# ESP32_with_USBC.net
KiCad netlist of a schematic drawn in Altium Designer
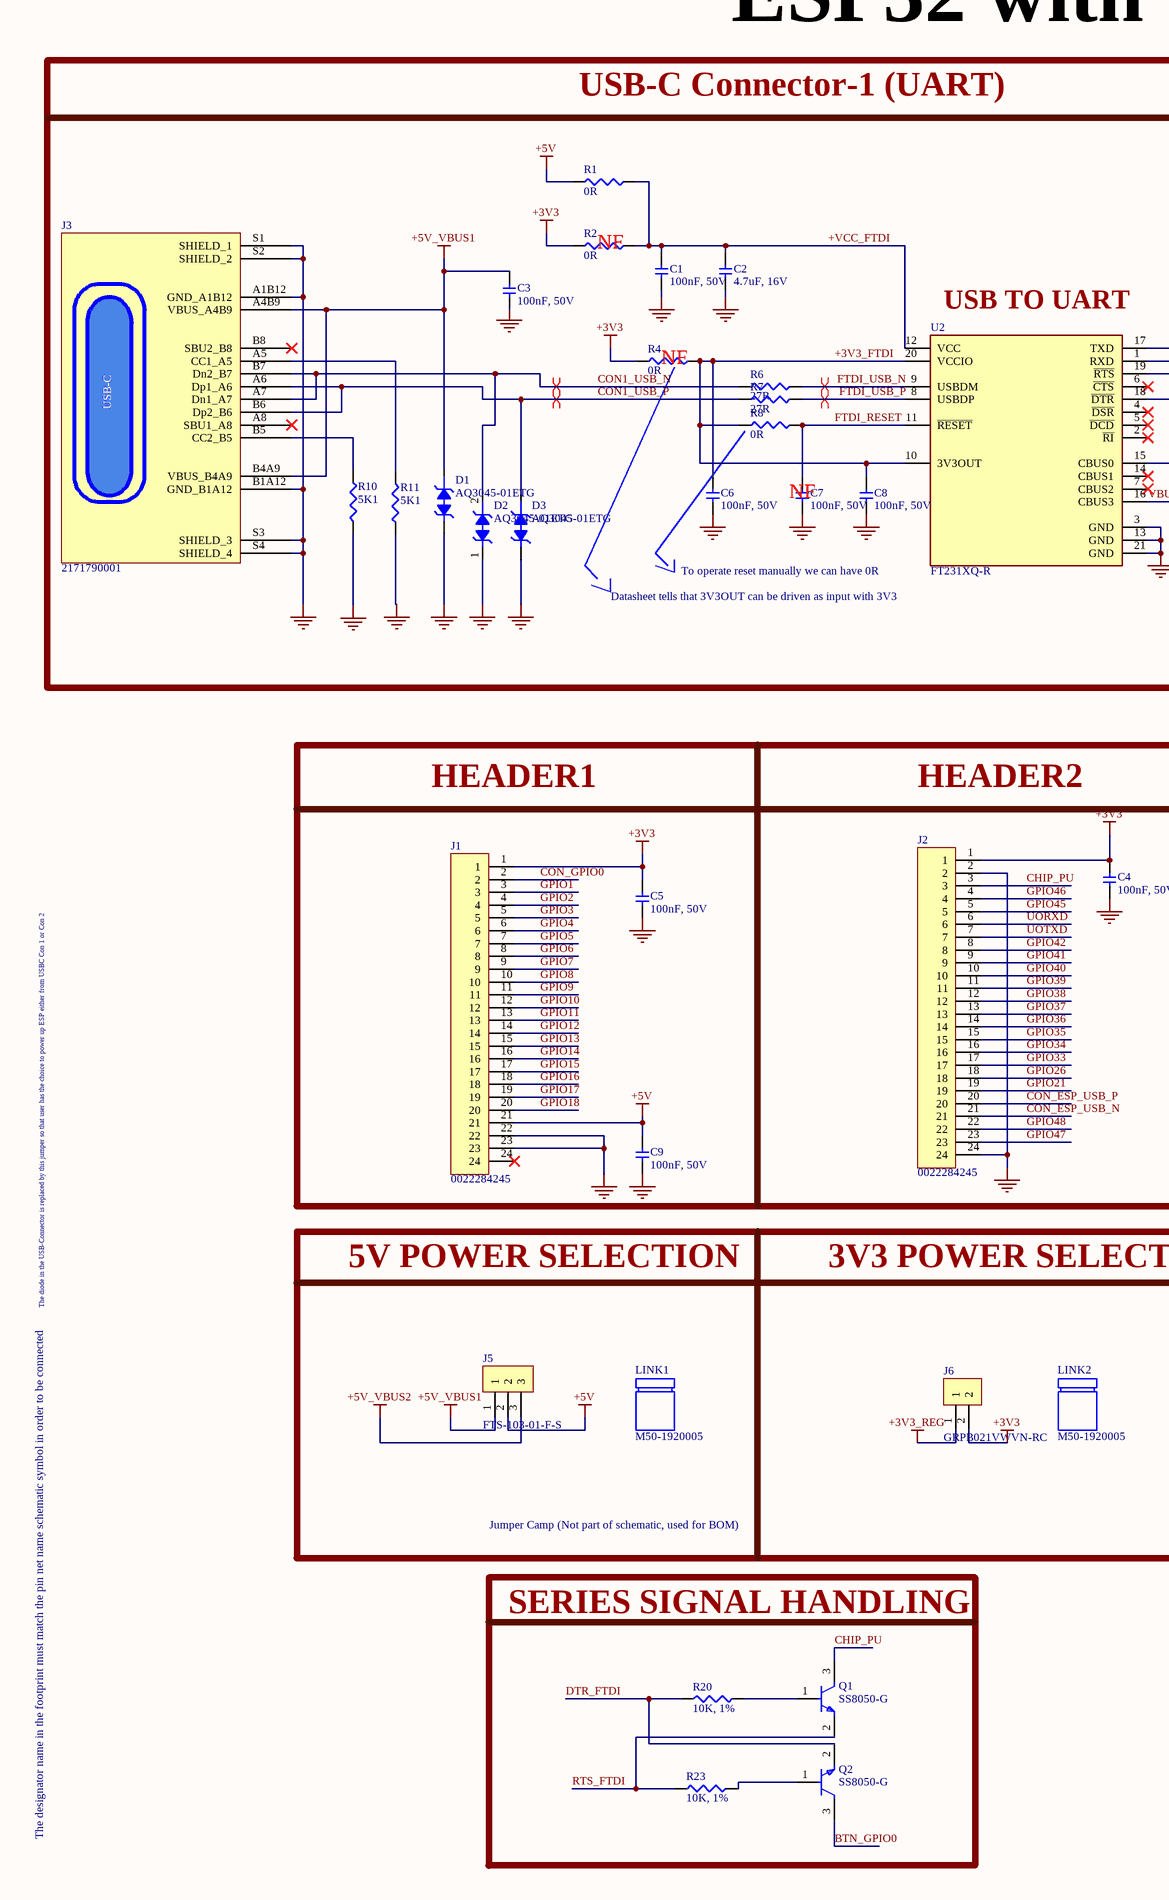
[diagram p0: ESP32 with USBC.SchDoc, left]
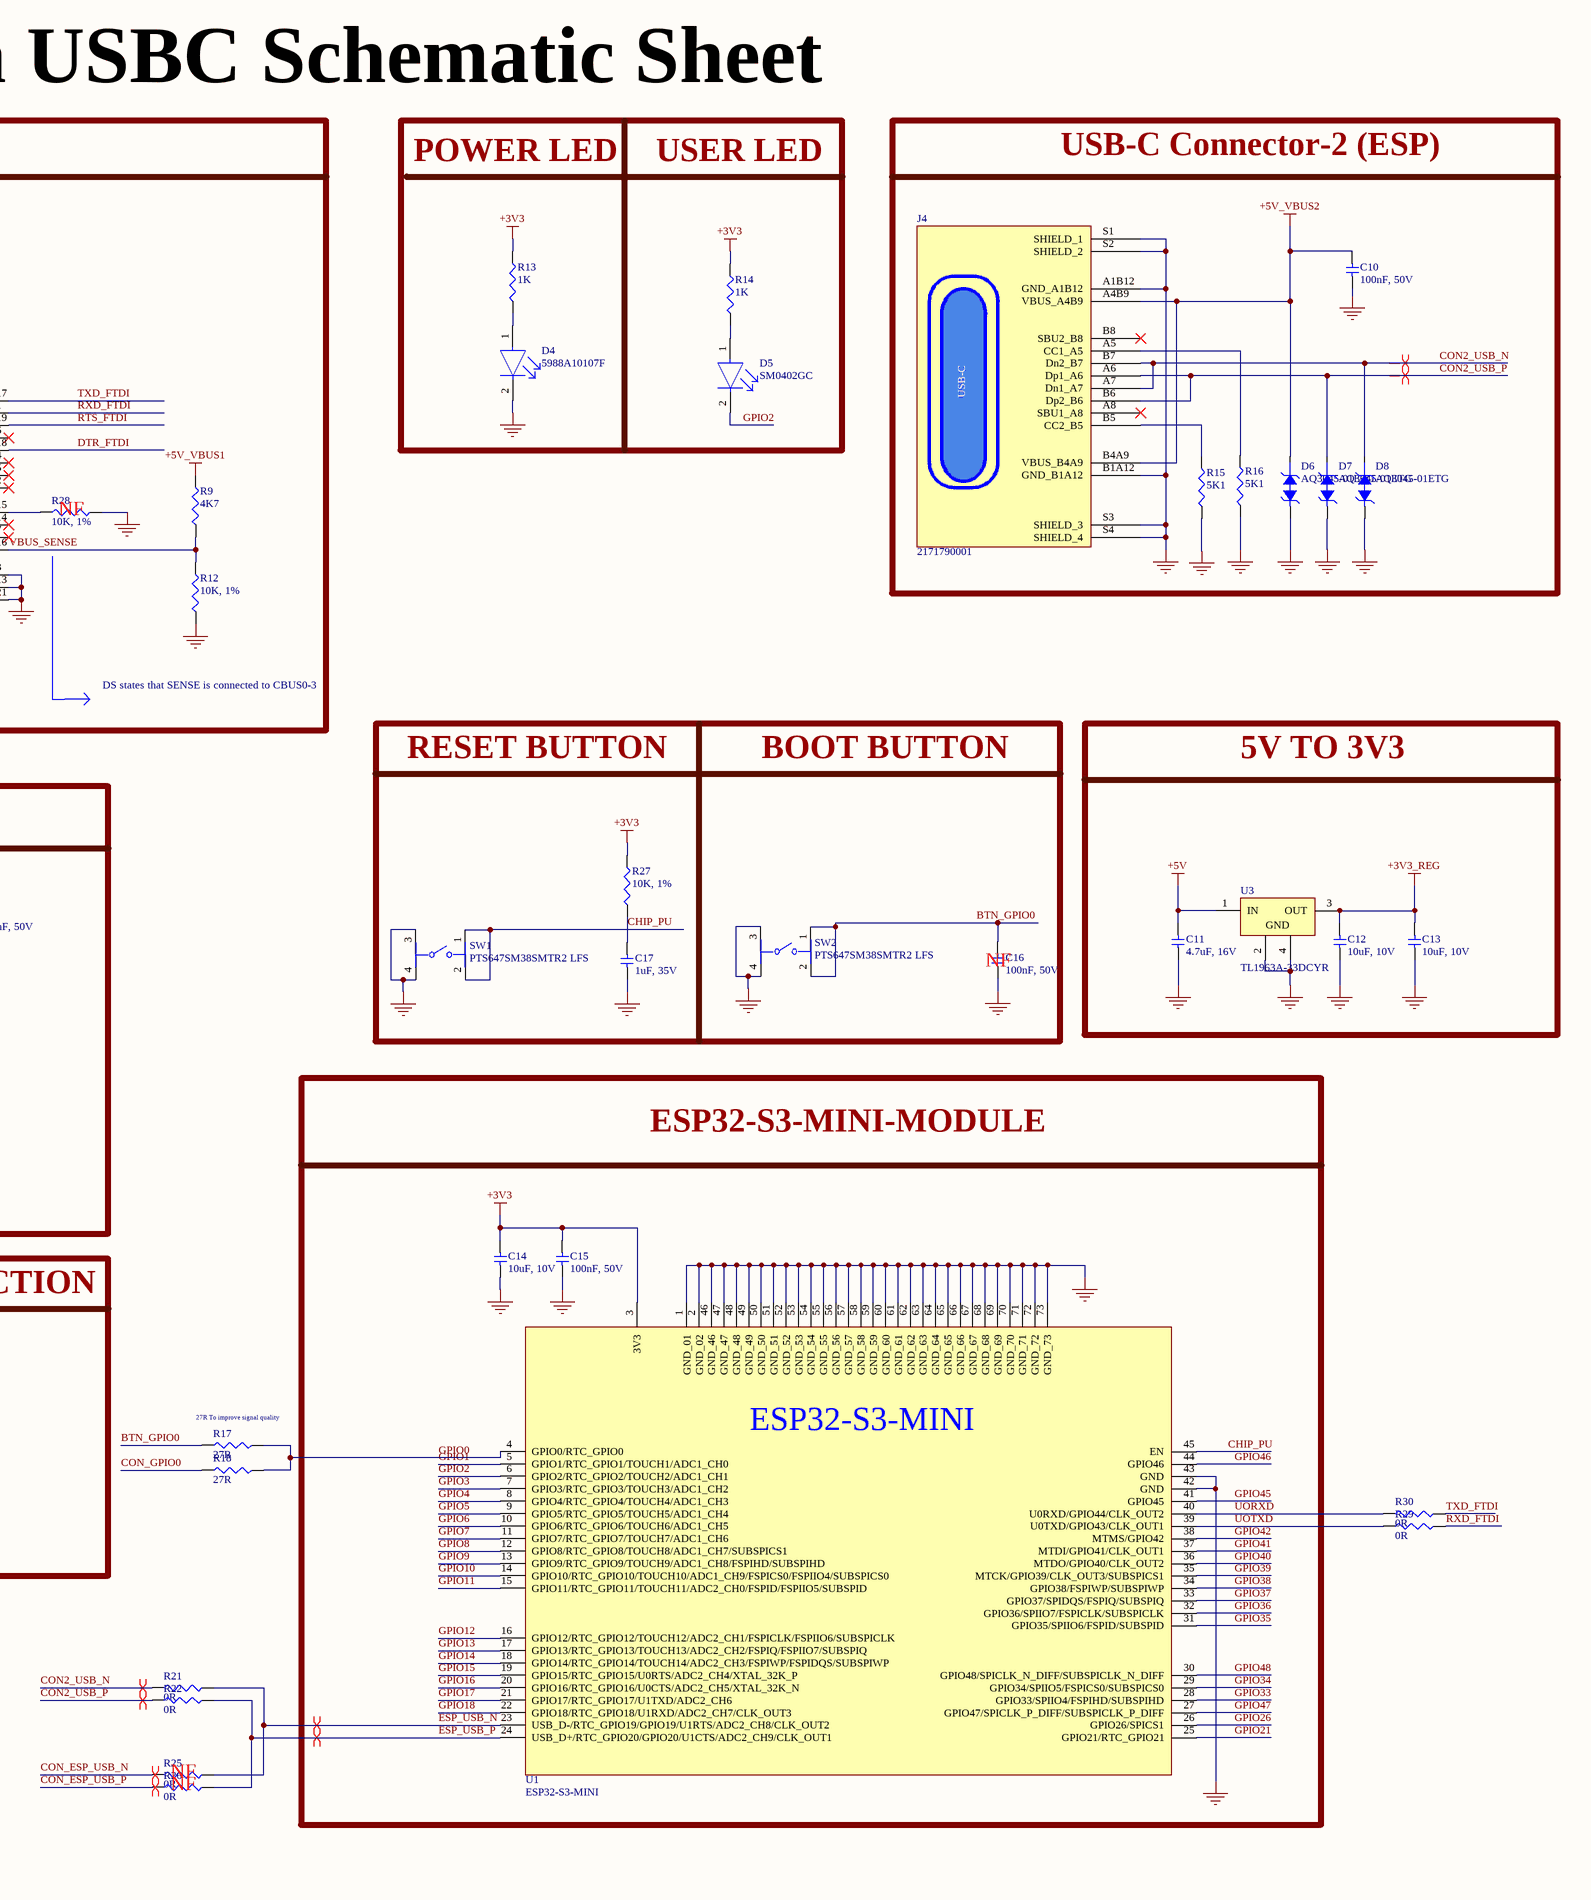
[diagram p1: ESP32 with USBC.SchDoc, right]

(export (version "E")
  (design (tool "Eeschema 10.0.6"))
  (components
    (comp (ref "C1")
      (value "100nF, 50V")
      (footprint "CAPC1005X55N")
      (description "10V 100nF X7R ±10% 0402 Multilayer Ceramic Capacitors MLCC - SMD/SMT ROHS")
      (fields
        (field (name "MANUFACTURER") "Samsung")
        (field (name "MANUFACTURER PART NUMBER") "CL05B104KP5NNNC")
      )
      (libsource (lib "Schlib") (part "CL05B104KP5NNNC"))
    )
    (comp (ref "C2")
      (value "4.7uF, 16V")
      (footprint "CAPC1005X55N")
      (description "CAP CER 4.7UF 16V X5R 0402")
      (fields
        (field (name "MANUFACTURER") "Samsung")
        (field (name "MANUFACTURER PART NUMBER") "CL05A475MO5NUNC")
      )
      (libsource (lib "Schlib") (part "CL05A475MO5NUNC (2)"))
    )
    (comp (ref "C3")
      (value "100nF, 50V")
      (footprint "CAPC1005X55N")
      (description "10V 100nF X7R ±10% 0402 Multilayer Ceramic Capacitors MLCC - SMD/SMT ROHS")
      (fields
        (field (name "MANUFACTURER") "Samsung")
        (field (name "MANUFACTURER PART NUMBER") "CL05B104KP5NNNC")
      )
      (libsource (lib "Schlib") (part "CL05B104KP5NNNC"))
    )
    (comp (ref "C4")
      (value "100nF, 50V")
      (footprint "CAPC1005X55N")
      (description "10V 100nF X7R ±10% 0402 Multilayer Ceramic Capacitors MLCC - SMD/SMT ROHS")
      (fields
        (field (name "MANUFACTURER") "Samsung")
        (field (name "MANUFACTURER PART NUMBER") "CL05B104KP5NNNC")
      )
      (libsource (lib "Schlib") (part "CL05B104KP5NNNC"))
    )
    (comp (ref "C5")
      (value "100nF, 50V")
      (footprint "CAPC1005X55N")
      (description "10V 100nF X7R ±10% 0402 Multilayer Ceramic Capacitors MLCC - SMD/SMT ROHS")
      (fields
        (field (name "MANUFACTURER") "Samsung")
        (field (name "MANUFACTURER PART NUMBER") "CL05B104KP5NNNC")
      )
      (libsource (lib "Schlib") (part "CL05B104KP5NNNC"))
    )
    (comp (ref "C6")
      (value "100nF, 50V")
      (footprint "CAPC1005X55N")
      (description "10V 100nF X7R ±10% 0402 Multilayer Ceramic Capacitors MLCC - SMD/SMT ROHS")
      (fields
        (field (name "MANUFACTURER") "Samsung")
        (field (name "MANUFACTURER PART NUMBER") "CL05B104KP5NNNC")
      )
      (libsource (lib "Schlib") (part "CL05B104KP5NNNC"))
    )
    (comp (ref "C7")
      (value "100nF, 50V")
      (footprint "CAPC1005X55N")
      (description "10V 100nF X7R ±10% 0402 Multilayer Ceramic Capacitors MLCC - SMD/SMT ROHS")
      (fields
        (field (name "MANUFACTURER") "Samsung")
        (field (name "MANUFACTURER PART NUMBER") "CL05B104KP5NNNC")
      )
      (libsource (lib "Schlib") (part "CL05B104KP5NNNC"))
    )
    (comp (ref "C8")
      (value "100nF, 50V")
      (footprint "CAPC1005X55N")
      (description "10V 100nF X7R ±10% 0402 Multilayer Ceramic Capacitors MLCC - SMD/SMT ROHS")
      (fields
        (field (name "MANUFACTURER") "Samsung")
        (field (name "MANUFACTURER PART NUMBER") "CL05B104KP5NNNC")
      )
      (libsource (lib "Schlib") (part "CL05B104KP5NNNC"))
    )
    (comp (ref "C9")
      (value "100nF, 50V")
      (footprint "CAPC1005X55N")
      (description "10V 100nF X7R ±10% 0402 Multilayer Ceramic Capacitors MLCC - SMD/SMT ROHS")
      (fields
        (field (name "MANUFACTURER") "Samsung")
        (field (name "MANUFACTURER PART NUMBER") "CL05B104KP5NNNC")
      )
      (libsource (lib "Schlib") (part "CL05B104KP5NNNC"))
    )
    (comp (ref "C10")
      (value "100nF, 50V")
      (footprint "CAPC1005X55N")
      (description "10V 100nF X7R ±10% 0402 Multilayer Ceramic Capacitors MLCC - SMD/SMT ROHS")
      (fields
        (field (name "MANUFACTURER") "Samsung")
        (field (name "MANUFACTURER PART NUMBER") "CL05B104KP5NNNC")
      )
      (libsource (lib "Schlib") (part "CL05B104KP5NNNC"))
    )
    (comp (ref "C11")
      (value "4.7uF, 16V")
      (footprint "CAPC1005X55N")
      (description "CAP CER 4.7UF 16V X5R 0402")
      (fields
        (field (name "MANUFACTURER") "Samsung")
        (field (name "MANUFACTURER PART NUMBER") "CL05A475MO5NUNC")
      )
      (libsource (lib "Schlib") (part "CL05A475MO5NUNC (2)"))
    )
    (comp (ref "C12")
      (value "10uF, 10V")
      (footprint "CAPC1005X55N")
      (description "10 µF ±20% 10V Ceramic Capacitor X5R 0402 (1005 Metric)")
      (fields
        (field (name "MANUFACTURER") "Samsung")
        (field (name "MANUFACTURER PART NUMBER") "CL05A106MP8NUB8")
      )
      (libsource (lib "Schlib") (part "CL05A106MP8NUB8"))
    )
    (comp (ref "C13")
      (value "10uF, 10V")
      (footprint "CAPC1005X55N")
      (description "10 µF ±20% 10V Ceramic Capacitor X5R 0402 (1005 Metric)")
      (fields
        (field (name "MANUFACTURER") "Samsung")
        (field (name "MANUFACTURER PART NUMBER") "CL05A106MP8NUB8")
      )
      (libsource (lib "Schlib") (part "CL05A106MP8NUB8"))
    )
    (comp (ref "C14")
      (value "10uF, 10V")
      (footprint "CAPC1005X55N")
      (description "10 µF ±20% 10V Ceramic Capacitor X5R 0402 (1005 Metric)")
      (fields
        (field (name "MANUFACTURER") "Samsung")
        (field (name "MANUFACTURER PART NUMBER") "CL05A106MP8NUB8")
      )
      (libsource (lib "Schlib") (part "CL05A106MP8NUB8"))
    )
    (comp (ref "C15")
      (value "100nF, 50V")
      (footprint "CAPC1005X55N")
      (description "10V 100nF X7R ±10% 0402 Multilayer Ceramic Capacitors MLCC - SMD/SMT ROHS")
      (fields
        (field (name "MANUFACTURER") "Samsung")
        (field (name "MANUFACTURER PART NUMBER") "CL05B104KP5NNNC")
      )
      (libsource (lib "Schlib") (part "CL05B104KP5NNNC"))
    )
    (comp (ref "C16")
      (value "100nF, 50V")
      (footprint "CAPC1005X55N")
      (description "10V 100nF X7R ±10% 0402 Multilayer Ceramic Capacitors MLCC - SMD/SMT ROHS")
      (fields
        (field (name "MANUFACTURER") "Samsung")
        (field (name "MANUFACTURER PART NUMBER") "CL05B104KP5NNNC")
      )
      (libsource (lib "Schlib") (part "CL05B104KP5NNNC"))
    )
    (comp (ref "C17")
      (value "1uF, 35V")
      (footprint "CAPC1005X55N")
      (description "CAP CER 1UF 35V X5R 0402")
      (fields
        (field (name "MANUFACTURER") "Samsung")
        (field (name "MANUFACTURER PART NUMBER") "CL05A105KL5NRNC")
      )
      (libsource (lib "Schlib") (part "CL05A105KL5NRNC"))
    )
    (comp (ref "D1")
      (value "AQ3045-01ETG")
      (footprint "SOD882")
      (description "TVS DIODE 5.3VWM 12VC SOD882")
      (fields (field (name "MANUFACTURER") "Littelfuse") (field (name "LCSC PART NUMBER") "C3710326"))
      (libsource (lib "Schlib") (part "AQ3045-01ETG"))
    )
    (comp (ref "D2")
      (value "AQ3045-01ETG")
      (footprint "SOD882")
      (description "TVS DIODE 5.3VWM 12VC SOD882")
      (fields (field (name "MANUFACTURER") "Littelfuse") (field (name "LCSC PART NUMBER") "C3710326"))
      (libsource (lib "") (part "AQ3045-01ETG_1"))
    )
    (comp (ref "D3")
      (value "AQ3045-01ETG")
      (footprint "SOD882")
      (description "TVS DIODE 5.3VWM 12VC SOD882")
      (fields (field (name "MANUFACTURER") "Littelfuse") (field (name "LCSC PART NUMBER") "C3710326"))
      (libsource (lib "Schlib") (part "AQ3045-01ETG"))
    )
    (comp (ref "D4")
      (value "5988A10107F")
      (footprint "5988A10107F")
      (description "LED RED 635NM 0402 SMD")
      (fields (field (name "MANUFACTURER") "Dialight") (field (name "LCSC PART NUMBER") "C6095258"))
      (libsource (lib "Schlib") (part "5988A10107F"))
    )
    (comp (ref "D5")
      (value "SM0402GC")
      (footprint "FP-SM0402GC-MFG")
      (description "LED GREEN CLEAR 0402 SMD")
      (fields (field (name "MANUFACTURER") "Bivar") (field (name "LCSC PART NUMBER") "C6488778"))
      (libsource (lib "Schlib") (part "SM0402GC"))
    )
    (comp (ref "D6")
      (value "AQ3045-01ETG")
      (footprint "SOD882")
      (description "TVS DIODE 5.3VWM 12VC SOD882")
      (fields (field (name "MANUFACTURER") "Littelfuse") (field (name "LCSC PART NUMBER") "C3710326"))
      (libsource (lib "Schlib") (part "AQ3045-01ETG"))
    )
    (comp (ref "D7")
      (value "AQ3045-01ETG")
      (footprint "SOD882")
      (description "TVS DIODE 5.3VWM 12VC SOD882")
      (fields (field (name "MANUFACTURER") "Littelfuse") (field (name "LCSC PART NUMBER") "C3710326"))
      (libsource (lib "Schlib") (part "AQ3045-01ETG"))
    )
    (comp (ref "D8")
      (value "AQ3045-01ETG")
      (footprint "SOD882")
      (description "TVS DIODE 5.3VWM 12VC SOD882")
      (fields (field (name "MANUFACTURER") "Littelfuse") (field (name "LCSC PART NUMBER") "C3710326"))
      (libsource (lib "Schlib") (part "AQ3045-01ETG"))
    )
    (comp (ref "J1")
      (value "0022284245")
      (footprint "HDR_1X24_2.54MM")
      (description "CONN HEADER VERT 24POS 2.54MM")
      (fields (field (name "MANUFACTURER") "Molex") (field (name "MANUFACTURER PART NUMBER") "22-28-4245"))
      (libsource (lib "Schlib") (part "22-28-4245"))
    )
    (comp (ref "J2")
      (value "0022284245")
      (footprint "HDR_1X24_2.54MM")
      (description "CONN HEADER VERT 24POS 2.54MM")
      (fields (field (name "MANUFACTURER") "Molex") (field (name "MANUFACTURER PART NUMBER") "22-28-4245"))
      (libsource (lib "Schlib") (part "22-28-4245"))
    )
    (comp (ref "J3")
      (value "2171790001")
      (footprint "FP-2171790001-MFG")
      (description "CONN RCP USB2.0 TYP C 24P SMD RA")
      (fields (field (name "MANUFACTURER") "Molex") (field (name "MANUFACTURER PART NUMBER") "217179-0001"))
      (libsource (lib "Schlib") (part "217179-0001"))
    )
    (comp (ref "J4")
      (value "2171790001")
      (footprint "FP-2171790001-MFG")
      (description "CONN RCP USB2.0 TYP C 24P SMD RA")
      (fields (field (name "MANUFACTURER") "Molex") (field (name "MANUFACTURER PART NUMBER") "217179-0001"))
      (libsource (lib "Schlib") (part "217179-0001"))
    )
    (comp (ref "J5")
      (value "FTS-103-01-F-S")
      (footprint "HDR_1X3_1.27MM")
      (description "CONN HEADER VERT 3POS 1.27MM")
      (fields (field (name "MANUFACTURER") "Samtec") (field (name "LCSC PART NUMBER") "C3333578"))
      (libsource (lib "Schlib") (part "FTS-103-01-F-S"))
    )
    (comp (ref "J6")
      (value "GRPB021VWVN-RC")
      (footprint "HDR_1X2_1.27MM")
      (description "CONN HEADER VERT 2POS 1.27MM")
      (fields (field (name "MANUFACTURER") "Sullins") (field (name "LCSC PART NUMBER") "C6050037"))
      (libsource (lib "Schlib") (part "GRPB021VWVN-RC"))
    )
    (comp (ref "LINK1")
      (value "M50-1920005")
      (description "CONN SHUNT 1.27MM RED")
      (fields (field (name "MANUFACTURER") "Harwin"))
      (libsource (lib "Schlib") (part "M50-1920005"))
    )
    (comp (ref "LINK2")
      (value "M50-1920005")
      (description "CONN SHUNT 1.27MM RED")
      (fields (field (name "MANUFACTURER") "Harwin"))
      (libsource (lib "Schlib") (part "M50-1920005"))
    )
    (comp (ref "Q1")
      (value "SS8050-G")
      (footprint "FP-SS8050-G-IPC_B")
      (description "TRANS NPN 25V 1.5A SOT-23-3")
      (fields (field (name "MANUFACTURER") "Comchip") (field (name "LCSC PART NUMBER") "C164886"))
      (libsource (lib "Schlib") (part "SS8050-G"))
    )
    (comp (ref "Q2")
      (value "SS8050-G")
      (footprint "FP-SS8050-G-IPC_B")
      (description "TRANS NPN 25V 1.5A SOT-23-3")
      (fields (field (name "MANUFACTURER") "Comchip") (field (name "LCSC PART NUMBER") "C164886"))
      (libsource (lib "Schlib") (part "SS8050-G"))
    )
    (comp (ref "R1")
      (value "0R")
      (footprint "RESC1005X37N")
      (description "RES 0 OHM JUMPER 1/16W 0402")
      (fields
        (field (name "MANUFACTURER") "Yageo")
        (field (name "MANUFACTURER PART NUMBER") "RC0402JR-070RL")
      )
      (libsource (lib "Schlib") (part "RC0402JR-070RL"))
    )
    (comp (ref "R2")
      (value "0R")
      (footprint "RESC1005X37N")
      (description "RES 0 OHM JUMPER 1/16W 0402")
      (fields
        (field (name "MANUFACTURER") "Yageo")
        (field (name "MANUFACTURER PART NUMBER") "RC0402JR-070RL")
      )
      (libsource (lib "Schlib") (part "RC0402JR-070RL"))
    )
    (comp (ref "R4")
      (value "0R")
      (footprint "RESC1005X37N")
      (description "RES 0 OHM JUMPER 1/16W 0402")
      (fields
        (field (name "MANUFACTURER") "Yageo")
        (field (name "MANUFACTURER PART NUMBER") "RC0402JR-070RL")
      )
      (libsource (lib "Schlib") (part "RC0402JR-070RL"))
    )
    (comp (ref "R6")
      (value "27R")
      (footprint "RESC1005X37N")
      (description "RES 27 OHM 5% 1/16W 0402")
      (fields
        (field (name "MANUFACTURER") "Yageo")
        (field (name "MANUFACTURER PART NUMBER") "RC0402JR-0727RL")
      )
      (libsource (lib "Schlib") (part "RC0402JR-0727RL"))
    )
    (comp (ref "R7")
      (value "27R")
      (footprint "RESC1005X37N")
      (description "RES 27 OHM 5% 1/16W 0402")
      (fields
        (field (name "MANUFACTURER") "Yageo")
        (field (name "MANUFACTURER PART NUMBER") "RC0402JR-0727RL")
      )
      (libsource (lib "Schlib") (part "RC0402JR-0727RL"))
    )
    (comp (ref "R8")
      (value "0R")
      (footprint "RESC1005X37N")
      (description "RES 0 OHM JUMPER 1/16W 0402")
      (fields
        (field (name "MANUFACTURER") "Yageo")
        (field (name "MANUFACTURER PART NUMBER") "RC0402JR-070RL")
      )
      (libsource (lib "Schlib") (part "RC0402JR-070RL"))
    )
    (comp (ref "R9")
      (value "4K7")
      (footprint "RESC1005X37N")
      (description "RES 4.7K OHM 1% 1/16W 0402")
      (fields
        (field (name "MANUFACTURER") "Yageo")
        (field (name "MANUFACTURER PART NUMBER") "RC0402FR-074K7L")
      )
      (libsource (lib "Schlib") (part "RC0402FR-074K7L"))
    )
    (comp (ref "R10")
      (value "5K1")
      (footprint "RESC1005X37N")
      (description "RES SMD 5.1K OHM 1% 1/16W 0402")
      (fields
        (field (name "MANUFACTURER") "Yageo")
        (field (name "MANUFACTURER PART NUMBER") "AC0402FR-075K1L")
      )
      (libsource (lib "Schlib") (part "AC0402FR-075K1L"))
    )
    (comp (ref "R11")
      (value "5K1")
      (footprint "RESC1005X37N")
      (description "RES SMD 5.1K OHM 1% 1/16W 0402")
      (fields
        (field (name "MANUFACTURER") "Yageo")
        (field (name "MANUFACTURER PART NUMBER") "AC0402FR-075K1L")
      )
      (libsource (lib "Schlib") (part "AC0402FR-075K1L"))
    )
    (comp (ref "R12")
      (value "10K, 1%")
      (footprint "RESC1005X37N")
      (description "RES SMD 10K OHM 1% 1/16W 0402")
      (fields
        (field (name "MANUFACTURER") "Yageo")
        (field (name "MANUFACTURER PART NUMBER") "AC0402FR-0710KL")
      )
      (libsource (lib "Schlib") (part "AC0402FR-0710KL"))
    )
    (comp (ref "R13")
      (value "1K")
      (footprint "RESC1005X37N")
      (description "RES 1K OHM 1% 1/16W 0402")
      (fields
        (field (name "MANUFACTURER") "Yageo")
        (field (name "MANUFACTURER PART NUMBER") "RC0402FR-071KL")
      )
      (libsource (lib "Schlib") (part "RC0402FR-071KL"))
    )
    (comp (ref "R14")
      (value "1K")
      (footprint "RESC1005X37N")
      (description "RES 1K OHM 1% 1/16W 0402")
      (fields
        (field (name "MANUFACTURER") "Yageo")
        (field (name "MANUFACTURER PART NUMBER") "RC0402FR-071KL")
      )
      (libsource (lib "Schlib") (part "RC0402FR-071KL"))
    )
    (comp (ref "R15")
      (value "5K1")
      (footprint "RESC1005X37N")
      (description "RES SMD 5.1K OHM 1% 1/16W 0402")
      (fields
        (field (name "MANUFACTURER") "Yageo")
        (field (name "MANUFACTURER PART NUMBER") "AC0402FR-075K1L")
      )
      (libsource (lib "Schlib") (part "AC0402FR-075K1L"))
    )
    (comp (ref "R16")
      (value "5K1")
      (footprint "RESC1005X37N")
      (description "RES SMD 5.1K OHM 1% 1/16W 0402")
      (fields
        (field (name "MANUFACTURER") "Yageo")
        (field (name "MANUFACTURER PART NUMBER") "AC0402FR-075K1L")
      )
      (libsource (lib "Schlib") (part "AC0402FR-075K1L"))
    )
    (comp (ref "R17")
      (value "27R")
      (footprint "RESC1005X37N")
      (description "RES 27 OHM 5% 1/16W 0402")
      (fields
        (field (name "MANUFACTURER") "Yageo")
        (field (name "MANUFACTURER PART NUMBER") "RC0402JR-0727RL")
      )
      (libsource (lib "Schlib") (part "RC0402JR-0727RL"))
    )
    (comp (ref "R18")
      (value "27R")
      (footprint "RESC1005X37N")
      (description "RES 27 OHM 5% 1/16W 0402")
      (fields
        (field (name "MANUFACTURER") "Yageo")
        (field (name "MANUFACTURER PART NUMBER") "RC0402JR-0727RL")
      )
      (libsource (lib "Schlib") (part "RC0402JR-0727RL"))
    )
    (comp (ref "R20")
      (value "10K, 1%")
      (footprint "RESC1005X37N")
      (description "RES SMD 10K OHM 1% 1/16W 0402")
      (fields
        (field (name "MANUFACTURER") "Yageo")
        (field (name "MANUFACTURER PART NUMBER") "AC0402FR-0710KL")
      )
      (libsource (lib "Schlib") (part "AC0402FR-0710KL"))
    )
    (comp (ref "R21")
      (value "0R")
      (footprint "RESC1005X37N")
      (description "RES 0 OHM JUMPER 1/16W 0402")
      (fields
        (field (name "MANUFACTURER") "Yageo")
        (field (name "MANUFACTURER PART NUMBER") "RC0402JR-070RL")
      )
      (libsource (lib "Schlib") (part "RC0402JR-070RL"))
    )
    (comp (ref "R22")
      (value "0R")
      (footprint "RESC1005X37N")
      (description "RES 0 OHM JUMPER 1/16W 0402")
      (fields
        (field (name "MANUFACTURER") "Yageo")
        (field (name "MANUFACTURER PART NUMBER") "RC0402JR-070RL")
      )
      (libsource (lib "Schlib") (part "RC0402JR-070RL"))
    )
    (comp (ref "R23")
      (value "10K, 1%")
      (footprint "RESC1005X37N")
      (description "RES SMD 10K OHM 1% 1/16W 0402")
      (fields
        (field (name "MANUFACTURER") "Yageo")
        (field (name "MANUFACTURER PART NUMBER") "AC0402FR-0710KL")
      )
      (libsource (lib "Schlib") (part "AC0402FR-0710KL"))
    )
    (comp (ref "R25")
      (value "0R")
      (footprint "RESC1005X37N")
      (description "RES 0 OHM JUMPER 1/16W 0402")
      (fields
        (field (name "MANUFACTURER") "Yageo")
        (field (name "MANUFACTURER PART NUMBER") "RC0402JR-070RL")
      )
      (libsource (lib "Schlib") (part "RC0402JR-070RL"))
    )
    (comp (ref "R26")
      (value "0R")
      (footprint "RESC1005X37N")
      (description "RES 0 OHM JUMPER 1/16W 0402")
      (fields
        (field (name "MANUFACTURER") "Yageo")
        (field (name "MANUFACTURER PART NUMBER") "RC0402JR-070RL")
      )
      (libsource (lib "Schlib") (part "RC0402JR-070RL"))
    )
    (comp (ref "R27")
      (value "10K, 1%")
      (footprint "RESC1005X37N")
      (description "RES SMD 10K OHM 1% 1/16W 0402")
      (fields
        (field (name "MANUFACTURER") "Yageo")
        (field (name "MANUFACTURER PART NUMBER") "AC0402FR-0710KL")
      )
      (libsource (lib "Schlib") (part "AC0402FR-0710KL"))
    )
    (comp (ref "R28")
      (value "10K, 1%")
      (footprint "RESC1005X37N")
      (description "RES SMD 10K OHM 1% 1/16W 0402")
      (fields
        (field (name "MANUFACTURER") "Yageo")
        (field (name "MANUFACTURER PART NUMBER") "AC0402FR-0710KL")
      )
      (libsource (lib "Schlib") (part "AC0402FR-0710KL"))
    )
    (comp (ref "R29")
      (value "0R")
      (footprint "RESC1005X37N")
      (description "RES 0 OHM JUMPER 1/16W 0402")
      (fields
        (field (name "MANUFACTURER") "Yageo")
        (field (name "MANUFACTURER PART NUMBER") "RC0402JR-070RL")
      )
      (libsource (lib "Schlib") (part "RC0402JR-070RL"))
    )
    (comp (ref "R30")
      (value "0R")
      (footprint "RESC1005X37N")
      (description "RES 0 OHM JUMPER 1/16W 0402")
      (fields
        (field (name "MANUFACTURER") "Yageo")
        (field (name "MANUFACTURER PART NUMBER") "RC0402JR-070RL")
      )
      (libsource (lib "Schlib") (part "RC0402JR-070RL"))
    )
    (comp (ref "SW1")
      (value "PTS647SM38SMTR2 LFS")
      (footprint "FP-PTS647SM38SMTR2LFS-MFG")
      (description "SWITCH TACTILE SPST-NO 0.05A 12V")
      (fields
        (field (name "MANUFACTURER") "ITT C&K")
        (field (name "MANUFACTURER PART NUMBER") "PTS647SM38SMTR2LFS")
      )
      (libsource (lib "Schlib") (part "PTS647SM38SMTR2LFS"))
    )
    (comp (ref "SW2")
      (value "PTS647SM38SMTR2 LFS")
      (footprint "FP-PTS647SM38SMTR2LFS-MFG")
      (description "SWITCH TACTILE SPST-NO 0.05A 12V")
      (fields
        (field (name "MANUFACTURER") "ITT C&K")
        (field (name "MANUFACTURER PART NUMBER") "PTS647SM38SMTR2LFS")
      )
      (libsource (lib "Schlib") (part "PTS647SM38SMTR2LFS"))
    )
    (comp (ref "U1")
      (value "ESP32-S3-MINI")
      (footprint "XCVR_ESP32-S3-MINI-1-N8")
      (description "SMD module, ESP32-S3FN8, 8 MB SPI flash, PCB antenna")
      (fields
        (field (name "MANUFACTURER") "Espressif Systems")
        (field (name "MANUFACTURER PART NUMBER") "ESP32-S3-MINI-1-N8")
      )
      (libsource (lib "Schlib") (part "ESP32-S3-MINI-1-N8"))
    )
    (comp (ref "U2")
      (value "FT231XQ-R")
      (footprint "FP-QFN-20-IPC_B")
      (description "IC USB SERIAL FULL UART 20QFNOS")
      (fields (field (name "MANUFACTURER") "FTDI") (field (name "LCSC PART NUMBER") "C132159"))
      (libsource (lib "Schlib") (part "FT231XQ-R"))
    )
    (comp (ref "U3")
      (value "TL1963A-33DCYR")
      (footprint "DCY0004A_N")
      (description "IC REG LIN 3.3V 1.5A SOT-223-4")
      (fields (field (name "MANUFACTURER") "Texas Instruments") (field (name "LCSC PART NUMBER") "C181262"))
      (libsource (lib "Schlib") (part "TL1963A-33DCYR"))
    )
  )
  (nets
    (net (code "1") (name "+3V3") (class "Default")
      (node (ref "C14") (pin "2") (pinfunction "2_2") (pintype "passive"))
      (node (ref "C15") (pin "2") (pinfunction "2_2") (pintype "passive"))
      (node (ref "C4") (pin "2") (pinfunction "2_2") (pintype "passive"))
      (node (ref "C5") (pin "2") (pinfunction "2_2") (pintype "passive"))
      (node (ref "J1") (pin "1") (pinfunction "1_1") (pintype "passive"))
      (node (ref "J2") (pin "1") (pinfunction "1_1") (pintype "passive"))
      (node (ref "J6") (pin "2") (pinfunction "2_2") (pintype "passive"))
      (node (ref "R13") (pin "2") (pinfunction "2_2") (pintype "passive"))
      (node (ref "R14") (pin "2") (pinfunction "2_2") (pintype "passive"))
      (node (ref "R2") (pin "1") (pinfunction "1_1") (pintype "passive"))
      (node (ref "R27") (pin "2") (pinfunction "2_2") (pintype "passive"))
      (node (ref "R4") (pin "1") (pinfunction "1_1") (pintype "passive"))
      (node (ref "U1") (pin "3") (pinfunction "3V3_3") (pintype "passive"))
    )
    (net (code "2") (name "+3V3_REG") (class "Default")
      (node (ref "C12") (pin "2") (pinfunction "2_2") (pintype "passive"))
      (node (ref "C13") (pin "2") (pinfunction "2_2") (pintype "passive"))
      (node (ref "J6") (pin "1") (pinfunction "1_1") (pintype "passive"))
      (node (ref "U3") (pin "3") (pinfunction "OUT_3") (pintype "power_in"))
    )
    (net (code "3") (name "+5V") (class "Default")
      (node (ref "C11") (pin "2") (pinfunction "2_2") (pintype "passive"))
      (node (ref "C9") (pin "2") (pinfunction "2_2") (pintype "passive"))
      (node (ref "J1") (pin "21") (pinfunction "21_21") (pintype "passive"))
      (node (ref "J5") (pin "2") (pinfunction "2_2") (pintype "passive"))
      (node (ref "R1") (pin "1") (pinfunction "1_1") (pintype "passive"))
      (node (ref "U3") (pin "1") (pinfunction "IN_1") (pintype "power_in"))
    )
    (net (code "4") (name "+5V_VBUS1") (class "Default")
      (node (ref "C3") (pin "2") (pinfunction "2_2") (pintype "passive"))
      (node (ref "D1") (pin "2") (pinfunction "2_2") (pintype "passive"))
      (node (ref "J3") (pin "A4B9") (pinfunction "VBUS_A4B9_A4B9") (pintype "passive"))
      (node (ref "J3") (pin "B4A9") (pinfunction "VBUS_B4A9_B4A9") (pintype "passive"))
      (node (ref "J5") (pin "1") (pinfunction "1_1") (pintype "passive"))
      (node (ref "R9") (pin "2") (pinfunction "2_2") (pintype "passive"))
    )
    (net (code "5") (name "+5V_VBUS2") (class "Default")
      (node (ref "C10") (pin "2") (pinfunction "2_2") (pintype "passive"))
      (node (ref "D6") (pin "2") (pinfunction "2_2") (pintype "passive"))
      (node (ref "J4") (pin "A4B9") (pinfunction "VBUS_A4B9_A4B9") (pintype "passive"))
      (node (ref "J4") (pin "B4A9") (pinfunction "VBUS_B4A9_B4A9") (pintype "passive"))
      (node (ref "J5") (pin "3") (pinfunction "3_3") (pintype "passive"))
    )
    (net (code "6") (name "/+3V3_FTDI") (class "Default")
      (node (ref "C6") (pin "2") (pinfunction "2_2") (pintype "passive"))
      (node (ref "C8") (pin "2") (pinfunction "2_2") (pintype "passive"))
      (node (ref "R4") (pin "2") (pinfunction "2_2") (pintype "passive"))
      (node (ref "R8") (pin "1") (pinfunction "1_1") (pintype "passive"))
      (node (ref "U2") (pin "10") (pinfunction "3V3OUT_10") (pintype "passive"))
      (node (ref "U2") (pin "20") (pinfunction "VCCIO_20") (pintype "passive"))
    )
    (net (code "7") (name "/+VCC_FTDI") (class "Default")
      (node (ref "C1") (pin "2") (pinfunction "2_2") (pintype "passive"))
      (node (ref "C2") (pin "2") (pinfunction "2_2") (pintype "passive"))
      (node (ref "R1") (pin "2") (pinfunction "2_2") (pintype "passive"))
      (node (ref "R2") (pin "2") (pinfunction "2_2") (pintype "passive"))
      (node (ref "U2") (pin "12") (pinfunction "VCC_12") (pintype "passive"))
    )
    (net (code "8") (name "/BTN_GPIO0") (class "Default")
      (node (ref "C16") (pin "2") (pinfunction "2_2") (pintype "passive"))
      (node (ref "Q2") (pin "3") (pinfunction "C_3") (pintype "passive"))
      (node (ref "R17") (pin "1") (pinfunction "1_1") (pintype "passive"))
      (node (ref "SW2") (pin "1") (pinfunction "1_1") (pintype "passive"))
      (node (ref "SW2") (pin "2") (pinfunction "2_2") (pintype "passive"))
    )
    (net (code "9") (name "/CHIP_PU") (class "Default")
      (node (ref "C17") (pin "2") (pinfunction "2_2") (pintype "passive"))
      (node (ref "J2") (pin "3") (pinfunction "3_3") (pintype "passive"))
      (node (ref "Q1") (pin "3") (pinfunction "C_3") (pintype "passive"))
      (node (ref "R27") (pin "1") (pinfunction "1_1") (pintype "passive"))
      (node (ref "SW1") (pin "1") (pinfunction "1_1") (pintype "passive"))
      (node (ref "SW1") (pin "2") (pinfunction "2_2") (pintype "passive"))
      (node (ref "U1") (pin "45") (pinfunction "EN_45") (pintype "passive"))
    )
    (net (code "10") (name "/CON1_USB_N") (class "Default")
      (node (ref "D2") (pin "2") (pinfunction "2_2") (pintype "passive"))
      (node (ref "J3") (pin "A7") (pinfunction "Dn1_A7_A7") (pintype "passive"))
      (node (ref "J3") (pin "B7") (pinfunction "Dn2_B7_B7") (pintype "passive"))
      (node (ref "R6") (pin "1") (pinfunction "1_1") (pintype "passive"))
    )
    (net (code "11") (name "/CON1_USB_P") (class "Default")
      (node (ref "D3") (pin "2") (pinfunction "2_2") (pintype "passive"))
      (node (ref "J3") (pin "A6") (pinfunction "Dp1_A6_A6") (pintype "passive"))
      (node (ref "J3") (pin "B6") (pinfunction "Dp2_B6_B6") (pintype "passive"))
      (node (ref "R7") (pin "1") (pinfunction "1_1") (pintype "passive"))
    )
    (net (code "12") (name "/CON2_USB_N") (class "Default")
      (node (ref "D8") (pin "2") (pinfunction "2_2") (pintype "passive"))
      (node (ref "J4") (pin "A7") (pinfunction "Dn1_A7_A7") (pintype "passive"))
      (node (ref "J4") (pin "B7") (pinfunction "Dn2_B7_B7") (pintype "passive"))
      (node (ref "R21") (pin "1") (pinfunction "1_1") (pintype "passive"))
    )
    (net (code "13") (name "/CON2_USB_P") (class "Default")
      (node (ref "D7") (pin "2") (pinfunction "2_2") (pintype "passive"))
      (node (ref "J4") (pin "A6") (pinfunction "Dp1_A6_A6") (pintype "passive"))
      (node (ref "J4") (pin "B6") (pinfunction "Dp2_B6_B6") (pintype "passive"))
      (node (ref "R22") (pin "1") (pinfunction "1_1") (pintype "passive"))
    )
    (net (code "14") (name "/CON_ESP_USB_N") (class "Default")
      (node (ref "J2") (pin "21") (pinfunction "21_21") (pintype "passive"))
      (node (ref "R25") (pin "1") (pinfunction "1_1") (pintype "passive"))
    )
    (net (code "15") (name "/CON_ESP_USB_P") (class "Default")
      (node (ref "J2") (pin "20") (pinfunction "20_20") (pintype "passive"))
      (node (ref "R26") (pin "1") (pinfunction "1_1") (pintype "passive"))
    )
    (net (code "16") (name "/CON_GPIO0") (class "Default")
      (node (ref "J1") (pin "2") (pinfunction "2_2") (pintype "passive"))
      (node (ref "R18") (pin "1") (pinfunction "1_1") (pintype "passive"))
    )
    (net (code "17") (name "/DTR_FTDI") (class "Default")
      (node (ref "Q2") (pin "2") (pinfunction "E_2") (pintype "passive"))
      (node (ref "R20") (pin "2") (pinfunction "2_2") (pintype "passive"))
      (node (ref "U2") (pin "18") (pinfunction "~{DTR}_18") (pintype "passive"))
    )
    (net (code "18") (name "/ESP_USB_N") (class "Default")
      (node (ref "R21") (pin "2") (pinfunction "2_2") (pintype "passive"))
      (node (ref "R25") (pin "2") (pinfunction "2_2") (pintype "passive"))
      (node (ref "U1") (pin "23") (pinfunction "USB_D-/RTC_GPIO19/GPIO19/U1RTS/ADC2_CH8/CLK_OUT2_23") (pintype "passive"))
    )
    (net (code "19") (name "/ESP_USB_P") (class "Default")
      (node (ref "R22") (pin "2") (pinfunction "2_2") (pintype "passive"))
      (node (ref "R26") (pin "2") (pinfunction "2_2") (pintype "passive"))
      (node (ref "U1") (pin "24") (pinfunction "USB_D+/RTC_GPIO20/GPIO20/U1CTS/ADC2_CH9/CLK_OUT1_24") (pintype "passive"))
    )
    (net (code "20") (name "/FTDI_RESET") (class "Default")
      (node (ref "C7") (pin "2") (pinfunction "2_2") (pintype "passive"))
      (node (ref "R8") (pin "2") (pinfunction "2_2") (pintype "passive"))
      (node (ref "U2") (pin "11") (pinfunction "~{RESET}_11") (pintype "passive"))
    )
    (net (code "21") (name "/FTDI_USB_N") (class "Default")
      (node (ref "R6") (pin "2") (pinfunction "2_2") (pintype "passive"))
      (node (ref "U2") (pin "9") (pinfunction "USBDM_9") (pintype "passive"))
    )
    (net (code "22") (name "/FTDI_USB_P") (class "Default")
      (node (ref "R7") (pin "2") (pinfunction "2_2") (pintype "passive"))
      (node (ref "U2") (pin "8") (pinfunction "USBDP_8") (pintype "passive"))
    )
    (net (code "23") (name "/GPIO0") (class "Default")
      (node (ref "R17") (pin "2") (pinfunction "2_2") (pintype "passive"))
      (node (ref "R18") (pin "2") (pinfunction "2_2") (pintype "passive"))
      (node (ref "U1") (pin "4") (pinfunction "GPIO0/RTC_GPIO0_4") (pintype "passive"))
    )
    (net (code "24") (name "/GPIO1") (class "Default")
      (node (ref "J1") (pin "3") (pinfunction "3_3") (pintype "passive"))
      (node (ref "U1") (pin "5") (pinfunction "GPIO1/RTC_GPIO1/TOUCH1/ADC1_CH0_5") (pintype "passive"))
    )
    (net (code "25") (name "/GPIO2") (class "Default")
      (node (ref "D5") (pin "2") (pinfunction "C_2") (pintype "passive"))
      (node (ref "J1") (pin "4") (pinfunction "4_4") (pintype "passive"))
      (node (ref "U1") (pin "6") (pinfunction "GPIO2/RTC_GPIO2/TOUCH2/ADC1_CH1_6") (pintype "passive"))
    )
    (net (code "26") (name "/GPIO3") (class "Default")
      (node (ref "J1") (pin "5") (pinfunction "5_5") (pintype "passive"))
      (node (ref "U1") (pin "7") (pinfunction "GPIO3/RTC_GPIO3/TOUCH3/ADC1_CH2_7") (pintype "passive"))
    )
    (net (code "27") (name "/GPIO4") (class "Default")
      (node (ref "J1") (pin "6") (pinfunction "6_6") (pintype "passive"))
      (node (ref "U1") (pin "8") (pinfunction "GPIO4/RTC_GPIO4/TOUCH4/ADC1_CH3_8") (pintype "passive"))
    )
    (net (code "28") (name "/GPIO5") (class "Default")
      (node (ref "J1") (pin "7") (pinfunction "7_7") (pintype "passive"))
      (node (ref "U1") (pin "9") (pinfunction "GPIO5/RTC_GPIO5/TOUCH5/ADC1_CH4_9") (pintype "passive"))
    )
    (net (code "29") (name "/GPIO6") (class "Default")
      (node (ref "J1") (pin "8") (pinfunction "8_8") (pintype "passive"))
      (node (ref "U1") (pin "10") (pinfunction "GPIO6/RTC_GPIO6/TOUCH6/ADC1_CH5_10") (pintype "passive"))
    )
    (net (code "30") (name "/GPIO7") (class "Default")
      (node (ref "J1") (pin "9") (pinfunction "9_9") (pintype "passive"))
      (node (ref "U1") (pin "11") (pinfunction "GPIO7/RTC_GPIO7/TOUCH7/ADC1_CH6_11") (pintype "passive"))
    )
    (net (code "31") (name "/GPIO8") (class "Default")
      (node (ref "J1") (pin "10") (pinfunction "10_10") (pintype "passive"))
      (node (ref "U1") (pin "12") (pinfunction "GPIO8/RTC_GPIO8/TOUCH8/ADC1_CH7/SUBSPICS1_12") (pintype "passive"))
    )
    (net (code "32") (name "/GPIO9") (class "Default")
      (node (ref "J1") (pin "11") (pinfunction "11_11") (pintype "passive"))
      (node (ref "U1") (pin "13") (pinfunction "GPIO9/RTC_GPIO9/TOUCH9/ADC1_CH8/FSPIHD/SUBSPIHD_13") (pintype "passive"))
    )
    (net (code "33") (name "/GPIO10") (class "Default")
      (node (ref "J1") (pin "12") (pinfunction "12_12") (pintype "passive"))
      (node (ref "U1") (pin "14") (pinfunction "GPIO10/RTC_GPIO10/TOUCH10/ADC1_CH9/FSPICS0/FSPIIO4/SUBSPICS0_14") (pintype "passive"))
    )
    (net (code "34") (name "/GPIO11") (class "Default")
      (node (ref "J1") (pin "13") (pinfunction "13_13") (pintype "passive"))
      (node (ref "U1") (pin "15") (pinfunction "GPIO11/RTC_GPIO11/TOUCH11/ADC2_CH0/FSPID/FSPIIO5/SUBSPID_15") (pintype "passive"))
    )
    (net (code "35") (name "/GPIO12") (class "Default")
      (node (ref "J1") (pin "14") (pinfunction "14_14") (pintype "passive"))
      (node (ref "U1") (pin "16") (pinfunction "GPIO12/RTC_GPIO12/TOUCH12/ADC2_CH1/FSPICLK/FSPIIO6/SUBSPICLK_16") (pintype "passive"))
    )
    (net (code "36") (name "/GPIO13") (class "Default")
      (node (ref "J1") (pin "15") (pinfunction "15_15") (pintype "passive"))
      (node (ref "U1") (pin "17") (pinfunction "GPIO13/RTC_GPIO13/TOUCH13/ADC2_CH2/FSPIQ/FSPIIO7/SUBSPIQ_17") (pintype "passive"))
    )
    (net (code "37") (name "/GPIO14") (class "Default")
      (node (ref "J1") (pin "16") (pinfunction "16_16") (pintype "passive"))
      (node (ref "U1") (pin "18") (pinfunction "GPIO14/RTC_GPIO14/TOUCH14/ADC2_CH3/FSPIWP/FSPIDQS/SUBSPIWP_18") (pintype "passive"))
    )
    (net (code "38") (name "/GPIO15") (class "Default")
      (node (ref "J1") (pin "17") (pinfunction "17_17") (pintype "passive"))
      (node (ref "U1") (pin "19") (pinfunction "GPIO15/RTC_GPIO15/U0RTS/ADC2_CH4/XTAL_32K_P_19") (pintype "passive"))
    )
    (net (code "39") (name "/GPIO16") (class "Default")
      (node (ref "J1") (pin "18") (pinfunction "18_18") (pintype "passive"))
      (node (ref "U1") (pin "20") (pinfunction "GPIO16/RTC_GPIO16/U0CTS/ADC2_CH5/XTAL_32K_N_20") (pintype "passive"))
    )
    (net (code "40") (name "/GPIO17") (class "Default")
      (node (ref "J1") (pin "19") (pinfunction "19_19") (pintype "passive"))
      (node (ref "U1") (pin "21") (pinfunction "GPIO17/RTC_GPIO17/U1TXD/ADC2_CH6_21") (pintype "passive"))
    )
    (net (code "41") (name "/GPIO18") (class "Default")
      (node (ref "J1") (pin "20") (pinfunction "20_20") (pintype "passive"))
      (node (ref "U1") (pin "22") (pinfunction "GPIO18/RTC_GPIO18/U1RXD/ADC2_CH7/CLK_OUT3_22") (pintype "passive"))
    )
    (net (code "42") (name "/GPIO21") (class "Default")
      (node (ref "J2") (pin "19") (pinfunction "19_19") (pintype "passive"))
      (node (ref "U1") (pin "25") (pinfunction "GPIO21/RTC_GPIO21_25") (pintype "passive"))
    )
    (net (code "43") (name "/GPIO26") (class "Default")
      (node (ref "J2") (pin "18") (pinfunction "18_18") (pintype "passive"))
      (node (ref "U1") (pin "26") (pinfunction "GPIO26/SPICS1_26") (pintype "passive"))
    )
    (net (code "44") (name "/GPIO33") (class "Default")
      (node (ref "J2") (pin "17") (pinfunction "17_17") (pintype "passive"))
      (node (ref "U1") (pin "28") (pinfunction "GPIO33/SPIIO4/FSPIHD/SUBSPIHD_28") (pintype "passive"))
    )
    (net (code "45") (name "/GPIO34") (class "Default")
      (node (ref "J2") (pin "16") (pinfunction "16_16") (pintype "passive"))
      (node (ref "U1") (pin "29") (pinfunction "GPIO34/SPIIO5/FSPICS0/SUBSPICS0_29") (pintype "passive"))
    )
    (net (code "46") (name "/GPIO35") (class "Default")
      (node (ref "J2") (pin "15") (pinfunction "15_15") (pintype "passive"))
      (node (ref "U1") (pin "31") (pinfunction "GPIO35/SPIIO6/FSPID/SUBSPID_31") (pintype "passive"))
    )
    (net (code "47") (name "/GPIO36") (class "Default")
      (node (ref "J2") (pin "14") (pinfunction "14_14") (pintype "passive"))
      (node (ref "U1") (pin "32") (pinfunction "GPIO36/SPIIO7/FSPICLK/SUBSPICLK_32") (pintype "passive"))
    )
    (net (code "48") (name "/GPIO37") (class "Default")
      (node (ref "J2") (pin "13") (pinfunction "13_13") (pintype "passive"))
      (node (ref "U1") (pin "33") (pinfunction "GPIO37/SPIDQS/FSPIQ/SUBSPIQ_33") (pintype "passive"))
    )
    (net (code "49") (name "/GPIO38") (class "Default")
      (node (ref "J2") (pin "12") (pinfunction "12_12") (pintype "passive"))
      (node (ref "U1") (pin "34") (pinfunction "GPIO38/FSPIWP/SUBSPIWP_34") (pintype "passive"))
    )
    (net (code "50") (name "/GPIO39") (class "Default")
      (node (ref "J2") (pin "11") (pinfunction "11_11") (pintype "passive"))
      (node (ref "U1") (pin "35") (pinfunction "MTCK/GPIO39/CLK_OUT3/SUBSPICS1_35") (pintype "passive"))
    )
    (net (code "51") (name "/GPIO40") (class "Default")
      (node (ref "J2") (pin "10") (pinfunction "10_10") (pintype "passive"))
      (node (ref "U1") (pin "36") (pinfunction "MTDO/GPIO40/CLK_OUT2_36") (pintype "passive"))
    )
    (net (code "52") (name "/GPIO41") (class "Default")
      (node (ref "J2") (pin "9") (pinfunction "9_9") (pintype "passive"))
      (node (ref "U1") (pin "37") (pinfunction "MTDI/GPIO41/CLK_OUT1_37") (pintype "passive"))
    )
    (net (code "53") (name "/GPIO42") (class "Default")
      (node (ref "J2") (pin "8") (pinfunction "8_8") (pintype "passive"))
      (node (ref "U1") (pin "38") (pinfunction "MTMS/GPIO42_38") (pintype "passive"))
    )
    (net (code "54") (name "/GPIO45") (class "Default")
      (node (ref "J2") (pin "5") (pinfunction "5_5") (pintype "passive"))
      (node (ref "U1") (pin "41") (pinfunction "GPIO45_41") (pintype "passive"))
    )
    (net (code "55") (name "/GPIO46") (class "Default")
      (node (ref "J2") (pin "4") (pinfunction "4_4") (pintype "passive"))
      (node (ref "U1") (pin "44") (pinfunction "GPIO46_44") (pintype "passive"))
    )
    (net (code "56") (name "/GPIO47") (class "Default")
      (node (ref "J2") (pin "23") (pinfunction "23_23") (pintype "passive"))
      (node (ref "U1") (pin "27") (pinfunction "GPIO47/SPICLK_P_DIFF/SUBSPICLK_P_DIFF_27") (pintype "passive"))
    )
    (net (code "57") (name "/GPIO48") (class "Default")
      (node (ref "J2") (pin "22") (pinfunction "22_22") (pintype "passive"))
      (node (ref "U1") (pin "30") (pinfunction "GPIO48/SPICLK_N_DIFF/SUBSPICLK_N_DIFF_30") (pintype "passive"))
    )
    (net (code "58") (name "/RTS_FTDI") (class "Default")
      (node (ref "Q1") (pin "2") (pinfunction "E_2") (pintype "passive"))
      (node (ref "R23") (pin "2") (pinfunction "2_2") (pintype "passive"))
      (node (ref "U2") (pin "19") (pinfunction "~{RTS}_19") (pintype "passive"))
    )
    (net (code "59") (name "/RXD_FTDI") (class "Default")
      (node (ref "R29") (pin "2") (pinfunction "2_2") (pintype "passive"))
      (node (ref "U2") (pin "1") (pinfunction "RXD_1") (pintype "passive"))
    )
    (net (code "60") (name "/TXD_FTDI") (class "Default")
      (node (ref "R30") (pin "2") (pinfunction "2_2") (pintype "passive"))
      (node (ref "U2") (pin "17") (pinfunction "TXD_17") (pintype "passive"))
    )
    (net (code "61") (name "/UORXD") (class "Default")
      (node (ref "J2") (pin "6") (pinfunction "6_6") (pintype "passive"))
      (node (ref "R30") (pin "1") (pinfunction "1_1") (pintype "passive"))
      (node (ref "U1") (pin "40") (pinfunction "U0RXD/GPIO44/CLK_OUT2_40") (pintype "passive"))
    )
    (net (code "62") (name "/UOTXD") (class "Default")
      (node (ref "J2") (pin "7") (pinfunction "7_7") (pintype "passive"))
      (node (ref "R29") (pin "1") (pinfunction "1_1") (pintype "passive"))
      (node (ref "U1") (pin "39") (pinfunction "U0TXD/GPIO43/CLK_OUT1_39") (pintype "passive"))
    )
    (net (code "63") (name "/VBUS_SENSE") (class "Default")
      (node (ref "R12") (pin "2") (pinfunction "2_2") (pintype "passive"))
      (node (ref "R9") (pin "1") (pinfunction "1_1") (pintype "passive"))
      (node (ref "U2") (pin "16") (pinfunction "CBUS3_16") (pintype "passive"))
    )
    (net (code "64") (name "GND") (class "Default")
      (node (ref "C1") (pin "1") (pinfunction "1_1") (pintype "passive"))
      (node (ref "C10") (pin "1") (pinfunction "1_1") (pintype "passive"))
      (node (ref "C11") (pin "1") (pinfunction "1_1") (pintype "passive"))
      (node (ref "C12") (pin "1") (pinfunction "1_1") (pintype "passive"))
      (node (ref "C13") (pin "1") (pinfunction "1_1") (pintype "passive"))
      (node (ref "C14") (pin "1") (pinfunction "1_1") (pintype "passive"))
      (node (ref "C15") (pin "1") (pinfunction "1_1") (pintype "passive"))
      (node (ref "C16") (pin "1") (pinfunction "1_1") (pintype "passive"))
      (node (ref "C17") (pin "1") (pinfunction "1_1") (pintype "passive"))
      (node (ref "C2") (pin "1") (pinfunction "1_1") (pintype "passive"))
      (node (ref "C3") (pin "1") (pinfunction "1_1") (pintype "passive"))
      (node (ref "C4") (pin "1") (pinfunction "1_1") (pintype "passive"))
      (node (ref "C5") (pin "1") (pinfunction "1_1") (pintype "passive"))
      (node (ref "C6") (pin "1") (pinfunction "1_1") (pintype "passive"))
      (node (ref "C7") (pin "1") (pinfunction "1_1") (pintype "passive"))
      (node (ref "C8") (pin "1") (pinfunction "1_1") (pintype "passive"))
      (node (ref "C9") (pin "1") (pinfunction "1_1") (pintype "passive"))
      (node (ref "D1") (pin "1") (pinfunction "1_1") (pintype "passive"))
      (node (ref "D2") (pin "1") (pinfunction "1_1") (pintype "passive"))
      (node (ref "D3") (pin "1") (pinfunction "1_1") (pintype "passive"))
      (node (ref "D4") (pin "2") (pinfunction "C_2") (pintype "passive"))
      (node (ref "D6") (pin "1") (pinfunction "1_1") (pintype "passive"))
      (node (ref "D7") (pin "1") (pinfunction "1_1") (pintype "passive"))
      (node (ref "D8") (pin "1") (pinfunction "1_1") (pintype "passive"))
      (node (ref "J1") (pin "22") (pinfunction "22_22") (pintype "passive"))
      (node (ref "J1") (pin "23") (pinfunction "23_23") (pintype "passive"))
      (node (ref "J2") (pin "2") (pinfunction "2_2") (pintype "passive"))
      (node (ref "J2") (pin "24") (pinfunction "24_24") (pintype "passive"))
      (node (ref "J3") (pin "A1B12") (pinfunction "GND_A1B12_A1B12") (pintype "passive"))
      (node (ref "J3") (pin "B1A12") (pinfunction "GND_B1A12_B1A12") (pintype "passive"))
      (node (ref "J3") (pin "S1") (pinfunction "SHIELD_1_S1") (pintype "passive"))
      (node (ref "J3") (pin "S2") (pinfunction "SHIELD_2_S2") (pintype "passive"))
      (node (ref "J3") (pin "S3") (pinfunction "SHIELD_3_S3") (pintype "passive"))
      (node (ref "J3") (pin "S4") (pinfunction "SHIELD_4_S4") (pintype "passive"))
      (node (ref "J4") (pin "A1B12") (pinfunction "GND_A1B12_A1B12") (pintype "passive"))
      (node (ref "J4") (pin "B1A12") (pinfunction "GND_B1A12_B1A12") (pintype "passive"))
      (node (ref "J4") (pin "S1") (pinfunction "SHIELD_1_S1") (pintype "passive"))
      (node (ref "J4") (pin "S2") (pinfunction "SHIELD_2_S2") (pintype "passive"))
      (node (ref "J4") (pin "S3") (pinfunction "SHIELD_3_S3") (pintype "passive"))
      (node (ref "J4") (pin "S4") (pinfunction "SHIELD_4_S4") (pintype "passive"))
      (node (ref "R10") (pin "1") (pinfunction "1_1") (pintype "passive"))
      (node (ref "R11") (pin "1") (pinfunction "1_1") (pintype "passive"))
      (node (ref "R12") (pin "1") (pinfunction "1_1") (pintype "passive"))
      (node (ref "R15") (pin "1") (pinfunction "1_1") (pintype "passive"))
      (node (ref "R16") (pin "1") (pinfunction "1_1") (pintype "passive"))
      (node (ref "R28") (pin "2") (pinfunction "2_2") (pintype "passive"))
      (node (ref "SW1") (pin "3") (pinfunction "3_3") (pintype "passive"))
      (node (ref "SW1") (pin "4") (pinfunction "4_4") (pintype "passive"))
      (node (ref "SW2") (pin "3") (pinfunction "3_3") (pintype "passive"))
      (node (ref "SW2") (pin "4") (pinfunction "4_4") (pintype "passive"))
      (node (ref "U1") (pin "1") (pinfunction "GND_01_1") (pintype "passive"))
      (node (ref "U1") (pin "2") (pinfunction "GND_02_2") (pintype "passive"))
      (node (ref "U1") (pin "42") (pinfunction "GND_42") (pintype "passive"))
      (node (ref "U1") (pin "43") (pinfunction "GND_43") (pintype "passive"))
      (node (ref "U1") (pin "46") (pinfunction "GND_46_46") (pintype "passive"))
      (node (ref "U1") (pin "47") (pinfunction "GND_47_47") (pintype "passive"))
      (node (ref "U1") (pin "48") (pinfunction "GND_48_48") (pintype "passive"))
      (node (ref "U1") (pin "49") (pinfunction "GND_49_49") (pintype "passive"))
      (node (ref "U1") (pin "50") (pinfunction "GND_50_50") (pintype "passive"))
      (node (ref "U1") (pin "51") (pinfunction "GND_51_51") (pintype "passive"))
      (node (ref "U1") (pin "52") (pinfunction "GND_52_52") (pintype "passive"))
      (node (ref "U1") (pin "53") (pinfunction "GND_53_53") (pintype "passive"))
      (node (ref "U1") (pin "54") (pinfunction "GND_54_54") (pintype "passive"))
      (node (ref "U1") (pin "55") (pinfunction "GND_55_55") (pintype "passive"))
      (node (ref "U1") (pin "56") (pinfunction "GND_56_56") (pintype "passive"))
      (node (ref "U1") (pin "57") (pinfunction "GND_57_57") (pintype "passive"))
      (node (ref "U1") (pin "58") (pinfunction "GND_58_58") (pintype "passive"))
      (node (ref "U1") (pin "59") (pinfunction "GND_59_59") (pintype "passive"))
      (node (ref "U1") (pin "60") (pinfunction "GND_60_60") (pintype "passive"))
      (node (ref "U1") (pin "61") (pinfunction "GND_61_61") (pintype "passive"))
      (node (ref "U1") (pin "62") (pinfunction "GND_62_62") (pintype "passive"))
      (node (ref "U1") (pin "63") (pinfunction "GND_63_63") (pintype "passive"))
      (node (ref "U1") (pin "64") (pinfunction "GND_64_64") (pintype "passive"))
      (node (ref "U1") (pin "65") (pinfunction "GND_65_65") (pintype "passive"))
      (node (ref "U1") (pin "66") (pinfunction "GND_66_66") (pintype "passive"))
      (node (ref "U1") (pin "67") (pinfunction "GND_67_67") (pintype "passive"))
      (node (ref "U1") (pin "68") (pinfunction "GND_68_68") (pintype "passive"))
      (node (ref "U1") (pin "69") (pinfunction "GND_69_69") (pintype "passive"))
      (node (ref "U1") (pin "70") (pinfunction "GND_70_70") (pintype "passive"))
      (node (ref "U1") (pin "71") (pinfunction "GND_71_71") (pintype "passive"))
      (node (ref "U1") (pin "72") (pinfunction "GND_72_72") (pintype "passive"))
      (node (ref "U1") (pin "73") (pinfunction "GND_73_73") (pintype "passive"))
      (node (ref "U2") (pin "13") (pinfunction "GND_13") (pintype "passive"))
      (node (ref "U2") (pin "21") (pinfunction "GND_21") (pintype "passive"))
      (node (ref "U2") (pin "3") (pinfunction "GND_3") (pintype "passive"))
      (node (ref "U3") (pin "2") (pinfunction "GND_2") (pintype "power_in"))
      (node (ref "U3") (pin "4") (pinfunction "GND_4") (pintype "power_in"))
    )
    (net (code "65") (name "Net-(D4-A)") (class "Default")
      (node (ref "D4") (pin "1") (pinfunction "A_1") (pintype "passive"))
      (node (ref "R13") (pin "1") (pinfunction "1_1") (pintype "passive"))
    )
    (net (code "66") (name "Net-(D5-A)") (class "Default")
      (node (ref "D5") (pin "1") (pinfunction "A_1") (pintype "passive"))
      (node (ref "R14") (pin "1") (pinfunction "1_1") (pintype "passive"))
    )
    (net (code "67") (name "Net-(J3-CC1_A5)") (class "Default")
      (node (ref "J3") (pin "A5") (pinfunction "CC1_A5_A5") (pintype "passive"))
      (node (ref "R11") (pin "2") (pinfunction "2_2") (pintype "passive"))
    )
    (net (code "68") (name "Net-(J3-CC2_B5)") (class "Default")
      (node (ref "J3") (pin "B5") (pinfunction "CC2_B5_B5") (pintype "passive"))
      (node (ref "R10") (pin "2") (pinfunction "2_2") (pintype "passive"))
    )
    (net (code "69") (name "Net-(J4-CC1_A5)") (class "Default")
      (node (ref "J4") (pin "A5") (pinfunction "CC1_A5_A5") (pintype "passive"))
      (node (ref "R16") (pin "2") (pinfunction "2_2") (pintype "passive"))
    )
    (net (code "70") (name "Net-(J4-CC2_B5)") (class "Default")
      (node (ref "J4") (pin "B5") (pinfunction "CC2_B5_B5") (pintype "passive"))
      (node (ref "R15") (pin "2") (pinfunction "2_2") (pintype "passive"))
    )
    (net (code "71") (name "Net-(Q1-B)") (class "Default")
      (node (ref "Q1") (pin "1") (pinfunction "B_1") (pintype "passive"))
      (node (ref "R20") (pin "1") (pinfunction "1_1") (pintype "passive"))
    )
    (net (code "72") (name "Net-(Q2-B)") (class "Default")
      (node (ref "Q2") (pin "1") (pinfunction "B_1") (pintype "passive"))
      (node (ref "R23") (pin "1") (pinfunction "1_1") (pintype "passive"))
    )
    (net (code "73") (name "Net-(U2-CBUS0)") (class "Default")
      (node (ref "R28") (pin "1") (pinfunction "1_1") (pintype "passive"))
      (node (ref "U2") (pin "15") (pinfunction "CBUS0_15") (pintype "passive"))
    )
    (net (code "74") (name "unconnected-(J1-Pad24)") (class "Default")
      (node (ref "J1") (pin "24") (pinfunction "24_24") (pintype "passive+no_connect"))
    )
    (net (code "75") (name "unconnected-(J3-SBU1_A8-PadA8)") (class "Default")
      (node (ref "J3") (pin "A8") (pinfunction "SBU1_A8_A8") (pintype "passive+no_connect"))
    )
    (net (code "76") (name "unconnected-(J3-SBU2_B8-PadB8)") (class "Default")
      (node (ref "J3") (pin "B8") (pinfunction "SBU2_B8_B8") (pintype "passive+no_connect"))
    )
    (net (code "77") (name "unconnected-(J4-SBU1_A8-PadA8)") (class "Default")
      (node (ref "J4") (pin "A8") (pinfunction "SBU1_A8_A8") (pintype "passive+no_connect"))
    )
    (net (code "78") (name "unconnected-(J4-SBU2_B8-PadB8)") (class "Default")
      (node (ref "J4") (pin "B8") (pinfunction "SBU2_B8_B8") (pintype "passive+no_connect"))
    )
    (net (code "79") (name "unconnected-(U2-CBUS1-Pad14)") (class "Default")
      (node (ref "U2") (pin "14") (pinfunction "CBUS1_14") (pintype "passive+no_connect"))
    )
    (net (code "80") (name "unconnected-(U2-CBUS2-Pad7)") (class "Default")
      (node (ref "U2") (pin "7") (pinfunction "CBUS2_7") (pintype "passive+no_connect"))
    )
    (net (code "81") (name "unconnected-(U2-~{CTS}-Pad6)") (class "Default")
      (node (ref "U2") (pin "6") (pinfunction "~{CTS}_6") (pintype "passive+no_connect"))
    )
    (net (code "82") (name "unconnected-(U2-~{DCD}-Pad5)") (class "Default")
      (node (ref "U2") (pin "5") (pinfunction "~{DCD}_5") (pintype "passive+no_connect"))
    )
    (net (code "83") (name "unconnected-(U2-~{DSR}-Pad4)") (class "Default")
      (node (ref "U2") (pin "4") (pinfunction "~{DSR}_4") (pintype "passive+no_connect"))
    )
    (net (code "84") (name "unconnected-(U2-~{RI}-Pad2)") (class "Default")
      (node (ref "U2") (pin "2") (pinfunction "~{RI}_2") (pintype "passive+no_connect"))
    )
  )
)
